# v0_4_4.net
KiCad netlist of a schematic drawn in EAGLE
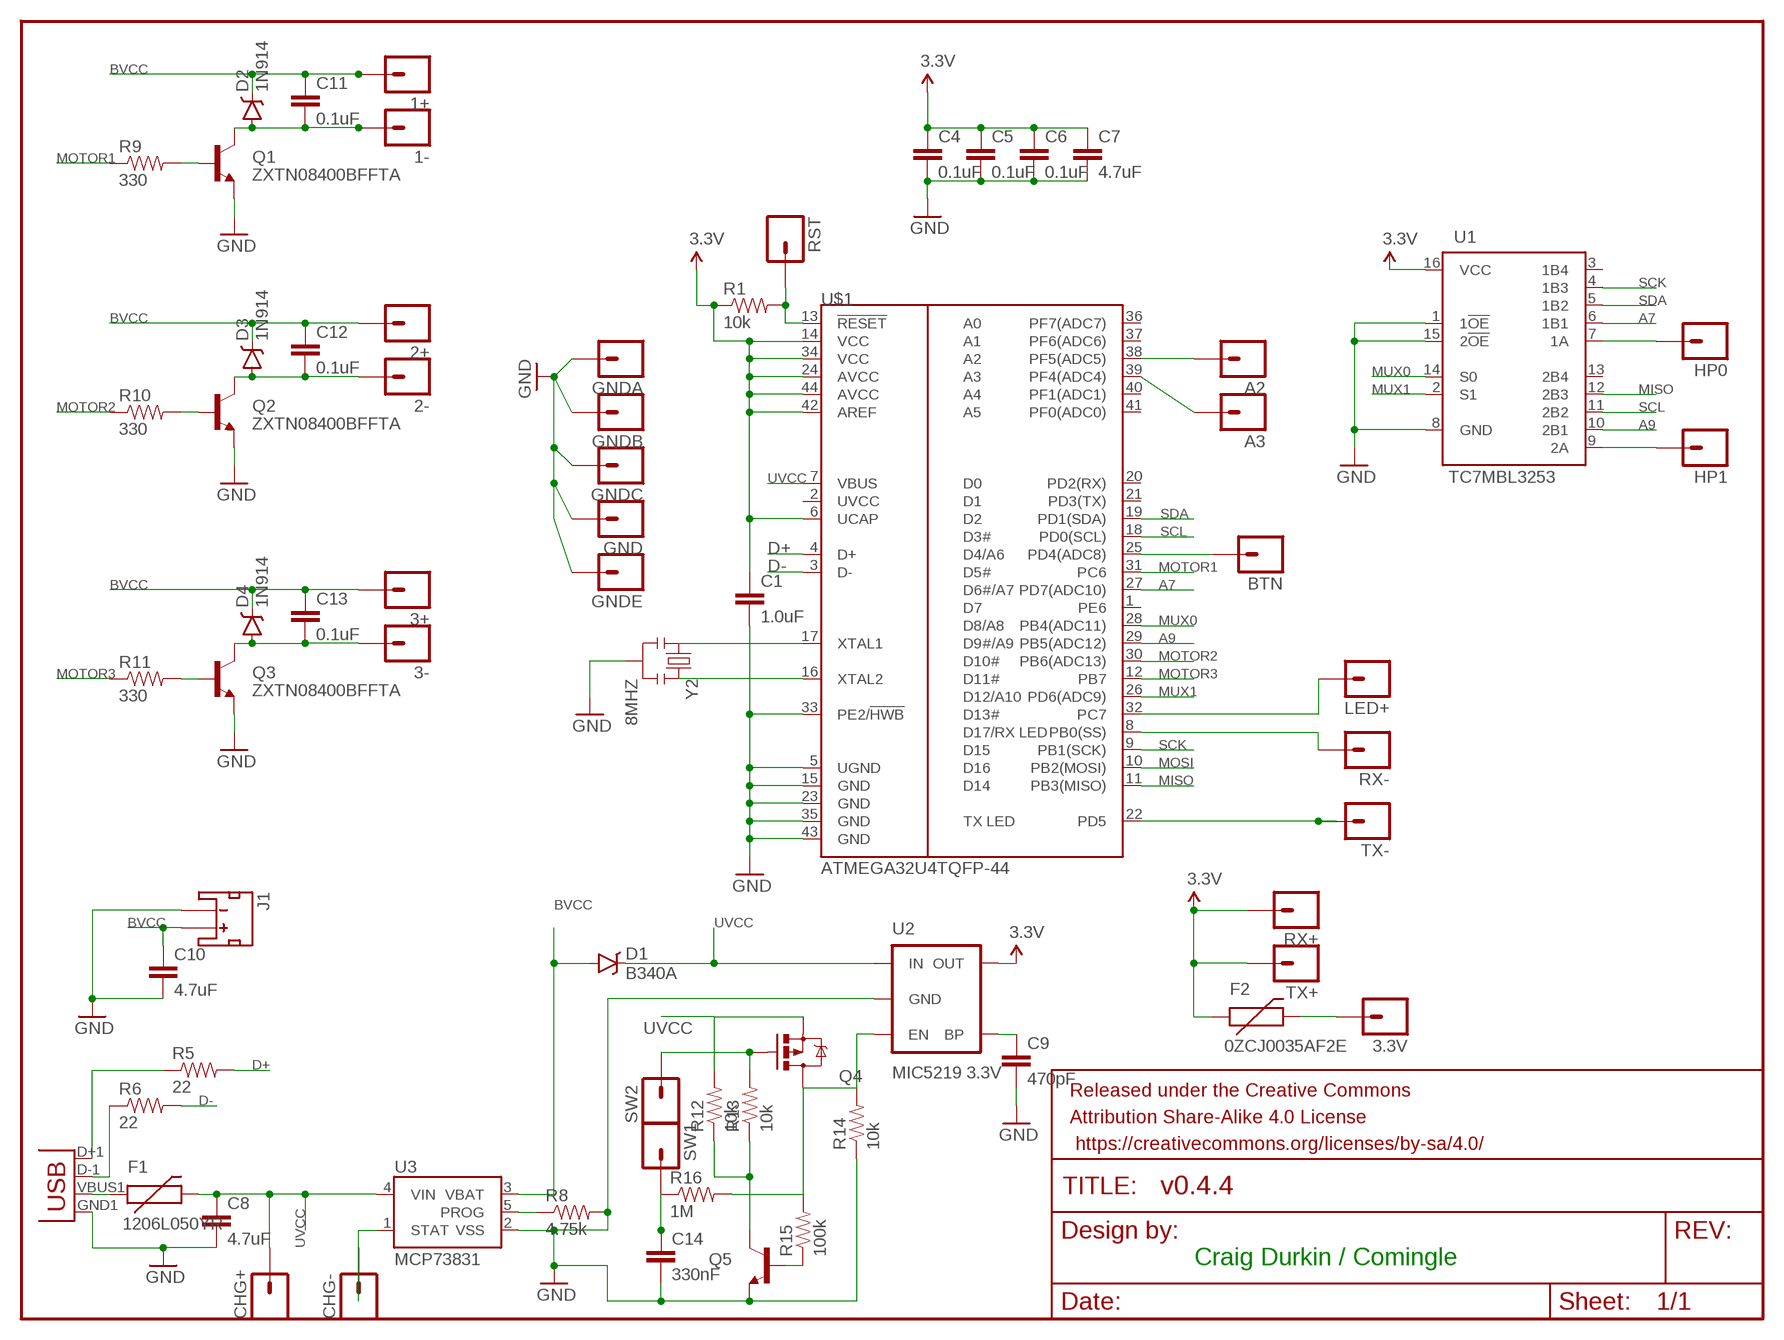
[diagram p0: schematic, sheet 1]

(export (version "E")
  (design (tool "Eeschema 10.0.6"))
  (components
    (comp (ref "1+")
      (value "M01PTH")
      (footprint "eagle-import:1X01")
      (libsource (lib "eagle-import") (part "M01PTH"))
    )
    (comp (ref "1-")
      (value "M01PTH")
      (footprint "eagle-import:1X01")
      (libsource (lib "eagle-import") (part "M01PTH"))
    )
    (comp (ref "2+")
      (value "M01PTH")
      (footprint "eagle-import:1X01")
      (libsource (lib "eagle-import") (part "M01PTH"))
    )
    (comp (ref "2-")
      (value "M01PTH")
      (footprint "eagle-import:1X01")
      (libsource (lib "eagle-import") (part "M01PTH"))
    )
    (comp (ref "3+")
      (value "M01PTH")
      (footprint "eagle-import:1X01")
      (libsource (lib "eagle-import") (part "M01PTH"))
    )
    (comp (ref "3-")
      (value "M01PTH")
      (footprint "eagle-import:1X01")
      (libsource (lib "eagle-import") (part "M01PTH"))
    )
    (comp (ref "3.3V")
      (value "M01PTH")
      (footprint "eagle-import:1X01")
      (libsource (lib "eagle-import") (part "M01PTH"))
    )
    (comp (ref "A2")
      (value "M01PTH")
      (footprint "eagle-import:1X01")
      (libsource (lib "eagle-import") (part "M01PTH"))
    )
    (comp (ref "A3")
      (value "M01PTH")
      (footprint "eagle-import:1X01")
      (libsource (lib "eagle-import") (part "M01PTH"))
    )
    (comp (ref "BTN")
      (value "M01PTH")
      (footprint "eagle-import:1X01")
      (libsource (lib "eagle-import") (part "M01PTH"))
    )
    (comp (ref "C1")
      (value "1.0uF")
      (footprint "eagle-import:0603-CAP")
      (libsource (lib "eagle-import") (part "CAP0603-CAP"))
    )
    (comp (ref "C4")
      (value "0.1uF")
      (footprint "eagle-import:0603-CAP")
      (libsource (lib "eagle-import") (part "SparkFun-Passives_CAP0603-CAP"))
    )
    (comp (ref "C5")
      (value "0.1uF")
      (footprint "eagle-import:0603-CAP")
      (libsource (lib "eagle-import") (part "SparkFun-Passives_CAP0603-CAP"))
    )
    (comp (ref "C6")
      (value "0.1uF")
      (footprint "eagle-import:0603-CAP")
      (libsource (lib "eagle-import") (part "SparkFun-Passives_CAP0603-CAP"))
    )
    (comp (ref "C7")
      (value "4.7uF")
      (footprint "eagle-import:0603-CAP")
      (libsource (lib "eagle-import") (part "SparkFun-Passives_CAP0603-CAP"))
    )
    (comp (ref "C8")
      (value "4.7uF")
      (footprint "eagle-import:1206")
      (libsource (lib "eagle-import") (part "SparkFun-Passives_CAP1206"))
    )
    (comp (ref "C9")
      (value "470pF")
      (footprint "eagle-import:0603-CAP")
      (libsource (lib "eagle-import") (part "CAP0603-CAP"))
    )
    (comp (ref "C10")
      (value "4.7uF")
      (footprint "eagle-import:1206")
      (libsource (lib "eagle-import") (part "SparkFun-Passives_CAP1206"))
    )
    (comp (ref "C11")
      (value "0.1uF")
      (footprint "eagle-import:0603-CAP")
      (libsource (lib "eagle-import") (part "CAP0603-CAP"))
    )
    (comp (ref "C12")
      (value "0.1uF")
      (footprint "eagle-import:0603-CAP")
      (libsource (lib "eagle-import") (part "CAP0603-CAP"))
    )
    (comp (ref "C13")
      (value "0.1uF")
      (footprint "eagle-import:0603-CAP")
      (libsource (lib "eagle-import") (part "CAP0603-CAP"))
    )
    (comp (ref "C14")
      (value "330nF")
      (footprint "eagle-import:0603-CAP")
      (libsource (lib "eagle-import") (part "CAP0603-CAP"))
    )
    (comp (ref "CHG+")
      (value "M01PTH")
      (footprint "eagle-import:1X01")
      (libsource (lib "eagle-import") (part "M01PTH"))
    )
    (comp (ref "CHG-")
      (value "M01PTH")
      (footprint "eagle-import:1X01")
      (libsource (lib "eagle-import") (part "M01PTH"))
    )
    (comp (ref "D1")
      (value "B340A")
      (footprint "eagle-import:SMA-DIODE")
      (libsource (lib "eagle-import") (part "DIODE-SCHOTTKY-B340A"))
    )
    (comp (ref "D2")
      (value "1N914")
      (footprint "eagle-import:SOD-323")
      (libsource (lib "eagle-import") (part "BAT20JFILM"))
    )
    (comp (ref "D3")
      (value "1N914")
      (footprint "eagle-import:SOD-323")
      (libsource (lib "eagle-import") (part "BAT20JFILM"))
    )
    (comp (ref "D4")
      (value "1N914")
      (footprint "eagle-import:SOD-323")
      (libsource (lib "eagle-import") (part "BAT20JFILM"))
    )
    (comp (ref "F1")
      (value "1206L050YR")
      (footprint "eagle-import:PTC-1206")
      (libsource (lib "eagle-import") (part "PTCSMD"))
    )
    (comp (ref "F2")
      (value "0ZCJ0035AF2E")
      (footprint "eagle-import:PTC-1206")
      (libsource (lib "eagle-import") (part "PTCSMD"))
    )
    (comp (ref "FRAME1")
      (value "FRAME-LETTER")
      (footprint "eagle-import:CREATIVE_COMMONS")
      (libsource (lib "eagle-import") (part "FRAME-LETTER"))
    )
    (comp (ref "GND")
      (value "M01PTH")
      (footprint "eagle-import:1X01")
      (libsource (lib "eagle-import") (part "M01PTH"))
    )
    (comp (ref "GNDA")
      (value "M01PTH")
      (footprint "eagle-import:1X01")
      (libsource (lib "eagle-import") (part "M01PTH"))
    )
    (comp (ref "GNDB")
      (value "M01PTH")
      (footprint "eagle-import:1X01")
      (libsource (lib "eagle-import") (part "M01PTH"))
    )
    (comp (ref "GNDC")
      (value "M01PTH")
      (footprint "eagle-import:1X01")
      (libsource (lib "eagle-import") (part "M01PTH"))
    )
    (comp (ref "GNDE")
      (value "M01PTH")
      (footprint "eagle-import:1X01")
      (libsource (lib "eagle-import") (part "M01PTH"))
    )
    (comp (ref "HP0")
      (value "M01PTH")
      (footprint "eagle-import:1X01")
      (libsource (lib "eagle-import") (part "M01PTH"))
    )
    (comp (ref "HP1")
      (value "M01PTH")
      (footprint "eagle-import:1X01")
      (libsource (lib "eagle-import") (part "M01PTH"))
    )
    (comp (ref "J1")
      (value "JST_2MM_MALE")
      (footprint "eagle-import:JST-2-SMD")
      (libsource (lib "eagle-import") (part "JST_2MM_MALE"))
    )
    (comp (ref "JP4")
      (value "USB")
      (footprint "eagle-import:USB-B-MICRO-SMD_V03")
      (libsource (lib "eagle-import") (part "USB"))
    )
    (comp (ref "LED+")
      (value "M01PTH")
      (footprint "eagle-import:1X01")
      (libsource (lib "eagle-import") (part "M01PTH"))
    )
    (comp (ref "Q1")
      (value "ZXTN08400BFFTA")
      (footprint "eagle-import:SOT23-3")
      (libsource (lib "eagle-import") (part "TRANSISTOR_NPNSOT23-3"))
    )
    (comp (ref "Q2")
      (value "ZXTN08400BFFTA")
      (footprint "eagle-import:SOT23-3")
      (libsource (lib "eagle-import") (part "TRANSISTOR_NPNSOT23-3"))
    )
    (comp (ref "Q3")
      (value "ZXTN08400BFFTA")
      (footprint "eagle-import:SOT23-3")
      (libsource (lib "eagle-import") (part "TRANSISTOR_NPNSOT23-3"))
    )
    (comp (ref "Q4")
      (value "NTS2101PT1G")
      (footprint "eagle-import:SOT23-3")
      (libsource (lib "eagle-import") (part "MOSFET-PCHANNEL"))
    )
    (comp (ref "Q5")
      (value "MMBT2222A")
      (footprint "eagle-import:SOT23-3")
      (libsource (lib "eagle-import") (part "TRANSISTOR_NPNMMBT2222A"))
    )
    (comp (ref "R1")
      (value "10k")
      (footprint "eagle-import:0603-RES")
      (libsource (lib "eagle-import") (part "RESISTOR0603-RES"))
    )
    (comp (ref "R5")
      (value "22")
      (footprint "eagle-import:0603-RES")
      (libsource (lib "eagle-import") (part "RESISTOR0603-RES"))
    )
    (comp (ref "R6")
      (value "22")
      (footprint "eagle-import:0603-RES")
      (libsource (lib "eagle-import") (part "RESISTOR0603-RES"))
    )
    (comp (ref "R8")
      (value "4.75k")
      (footprint "eagle-import:0603-RES")
      (libsource (lib "eagle-import") (part "RESISTOR0603-RES"))
    )
    (comp (ref "R9")
      (value "330")
      (footprint "eagle-import:0603-RES")
      (libsource (lib "eagle-import") (part "RESISTOR0603-RES"))
    )
    (comp (ref "R10")
      (value "330")
      (footprint "eagle-import:0603-RES")
      (libsource (lib "eagle-import") (part "RESISTOR0603-RES"))
    )
    (comp (ref "R11")
      (value "330")
      (footprint "eagle-import:0603-RES")
      (libsource (lib "eagle-import") (part "RESISTOR0603-RES"))
    )
    (comp (ref "R12")
      (value "10k")
      (footprint "eagle-import:0603-RES")
      (libsource (lib "eagle-import") (part "RESISTOR0603-RES"))
    )
    (comp (ref "R13")
      (value "10k")
      (footprint "eagle-import:0603-RES")
      (libsource (lib "eagle-import") (part "RESISTOR0603-RES"))
    )
    (comp (ref "R14")
      (value "10k")
      (footprint "eagle-import:0603-RES")
      (libsource (lib "eagle-import") (part "RESISTOR0603-RES"))
    )
    (comp (ref "R15")
      (value "100k")
      (footprint "eagle-import:0603-RES")
      (libsource (lib "eagle-import") (part "RESISTOR0603-RES"))
    )
    (comp (ref "R16")
      (value "1M")
      (footprint "eagle-import:0603-RES")
      (libsource (lib "eagle-import") (part "RESISTOR0603-RES"))
    )
    (comp (ref "RST")
      (value "M01PTH")
      (footprint "eagle-import:1X01")
      (libsource (lib "eagle-import") (part "M01PTH"))
    )
    (comp (ref "RX+")
      (value "M01PTH")
      (footprint "eagle-import:1X01")
      (libsource (lib "eagle-import") (part "M01PTH"))
    )
    (comp (ref "RX-")
      (value "M01PTH")
      (footprint "eagle-import:1X01")
      (libsource (lib "eagle-import") (part "M01PTH"))
    )
    (comp (ref "SW1")
      (value "M01PTH")
      (footprint "eagle-import:1X01")
      (libsource (lib "eagle-import") (part "M01PTH"))
    )
    (comp (ref "SW2")
      (value "M01PTH")
      (footprint "eagle-import:1X01")
      (libsource (lib "eagle-import") (part "M01PTH"))
    )
    (comp (ref "TX+")
      (value "M01PTH")
      (footprint "eagle-import:1X01")
      (libsource (lib "eagle-import") (part "M01PTH"))
    )
    (comp (ref "TX-")
      (value "M01PTH")
      (footprint "eagle-import:1X01")
      (libsource (lib "eagle-import") (part "M01PTH"))
    )
    (comp (ref "U$1")
      (value "ATMEGA32U4TQFP-44")
      (footprint "eagle-import:TQFP44")
      (libsource (lib "eagle-import") (part "ATMEGA32U4TQFP-44"))
    )
    (comp (ref "U1")
      (value "TC7MBL3253")
      (footprint "eagle-import:SSOP16-PRACTICE")
      (libsource (lib "eagle-import") (part "TC7MBL3253"))
    )
    (comp (ref "U2")
      (value "MIC5219 3.3V")
      (footprint "eagle-import:SOT23-5")
      (libsource (lib "eagle-import") (part "V_REG_MIC52193.3V"))
    )
    (comp (ref "U3")
      (value "MCP73831")
      (footprint "eagle-import:SOT23-5")
      (libsource (lib "eagle-import") (part "MCP73831"))
    )
    (comp (ref "Y2")
      (value "8MHZ")
      (footprint "eagle-import:RESONATOR-SMD")
      (libsource (lib "eagle-import") (part "RESONATOR8MHZ"))
    )
  )
  (nets
    (net (code "1") (name "/A7") (class "Default")
      (node (ref "U$1") (pin "27") (pinfunction "PD7(ADC10)_27") (pintype "bidirectional"))
      (node (ref "U1") (pin "6") (pinfunction "1B1_6") (pintype "bidirectional"))
    )
    (net (code "2") (name "/A9") (class "Default")
      (node (ref "U$1") (pin "29") (pinfunction "PB5(ADC12)_29") (pintype "bidirectional"))
      (node (ref "U1") (pin "10") (pinfunction "2B1_10") (pintype "bidirectional"))
    )
    (net (code "3") (name "/BVCC") (class "Default")
      (node (ref "1+") (pin "1") (pinfunction "1_1") (pintype "passive"))
      (node (ref "2+") (pin "1") (pinfunction "1_1") (pintype "passive"))
      (node (ref "3+") (pin "1") (pinfunction "1_1") (pintype "passive"))
      (node (ref "C10") (pin "1") (pinfunction "1_1") (pintype "passive"))
      (node (ref "C11") (pin "1") (pinfunction "1_1") (pintype "passive"))
      (node (ref "C12") (pin "1") (pinfunction "1_1") (pintype "passive"))
      (node (ref "C13") (pin "1") (pinfunction "1_1") (pintype "passive"))
      (node (ref "D1") (pin "A") (pinfunction "A_A") (pintype "passive"))
      (node (ref "D2") (pin "C") (pinfunction "C_C") (pintype "passive"))
      (node (ref "D3") (pin "C") (pinfunction "C_C") (pintype "passive"))
      (node (ref "D4") (pin "C") (pinfunction "C_C") (pintype "passive"))
      (node (ref "J1") (pin "2") (pinfunction "+_2") (pintype "bidirectional"))
      (node (ref "U3") (pin "3") (pinfunction "VBAT_3") (pintype "power_in"))
    )
    (net (code "4") (name "/D+") (class "Default")
      (node (ref "R5") (pin "2") (pinfunction "2_2") (pintype "passive"))
      (node (ref "U$1") (pin "4") (pinfunction "D+_4") (pintype "bidirectional"))
    )
    (net (code "5") (name "/D-") (class "Default")
      (node (ref "R6") (pin "2") (pinfunction "2_2") (pintype "passive"))
      (node (ref "U$1") (pin "3") (pinfunction "D-_3") (pintype "bidirectional"))
    )
    (net (code "6") (name "/MISO") (class "Default")
      (node (ref "U$1") (pin "11") (pinfunction "PB3(MISO)_11") (pintype "bidirectional"))
      (node (ref "U1") (pin "12") (pinfunction "2B3_12") (pintype "bidirectional"))
    )
    (net (code "7") (name "/MOSI") (class "Default")
      (node (ref "U$1") (pin "10") (pinfunction "PB2(MOSI)_10") (pintype "bidirectional"))
    )
    (net (code "8") (name "/MOTOR1") (class "Default")
      (node (ref "R9") (pin "1") (pinfunction "1_1") (pintype "passive"))
      (node (ref "U$1") (pin "31") (pinfunction "PC6_31") (pintype "bidirectional"))
    )
    (net (code "9") (name "/MOTOR2") (class "Default")
      (node (ref "R10") (pin "1") (pinfunction "1_1") (pintype "passive"))
      (node (ref "U$1") (pin "30") (pinfunction "PB6(ADC13)_30") (pintype "bidirectional"))
    )
    (net (code "10") (name "/MOTOR3") (class "Default")
      (node (ref "R11") (pin "1") (pinfunction "1_1") (pintype "passive"))
      (node (ref "U$1") (pin "12") (pinfunction "PB7_12") (pintype "bidirectional"))
    )
    (net (code "11") (name "/MUX0") (class "Default")
      (node (ref "U$1") (pin "28") (pinfunction "PB4(ADC11)_28") (pintype "bidirectional"))
      (node (ref "U1") (pin "14") (pinfunction "S0_14") (pintype "bidirectional"))
    )
    (net (code "12") (name "/MUX1") (class "Default")
      (node (ref "U$1") (pin "26") (pinfunction "PD6(ADC9)_26") (pintype "bidirectional"))
      (node (ref "U1") (pin "2") (pinfunction "S1_2") (pintype "bidirectional"))
    )
    (net (code "13") (name "/SCK") (class "Default")
      (node (ref "U$1") (pin "9") (pinfunction "PB1(SCK)_9") (pintype "bidirectional"))
      (node (ref "U1") (pin "4") (pinfunction "1B3_4") (pintype "bidirectional"))
    )
    (net (code "14") (name "/SCL") (class "Default")
      (node (ref "U$1") (pin "18") (pinfunction "PD0(SCL)_18") (pintype "bidirectional"))
      (node (ref "U1") (pin "11") (pinfunction "2B2_11") (pintype "bidirectional"))
    )
    (net (code "15") (name "/SDA") (class "Default")
      (node (ref "U$1") (pin "19") (pinfunction "PD1(SDA)_19") (pintype "bidirectional"))
      (node (ref "U1") (pin "5") (pinfunction "1B2_5") (pintype "bidirectional"))
    )
    (net (code "16") (name "/UVCC") (class "Default")
      (node (ref "C8") (pin "1") (pinfunction "1_1") (pintype "passive"))
      (node (ref "CHG+") (pin "1") (pinfunction "1_1") (pintype "passive"))
      (node (ref "D1") (pin "C") (pinfunction "C_C") (pintype "passive"))
      (node (ref "F1") (pin "2") (pinfunction "2_2") (pintype "bidirectional"))
      (node (ref "Q4") (pin "2") (pinfunction "S_2") (pintype "passive"))
      (node (ref "R12") (pin "2") (pinfunction "2_2") (pintype "passive"))
      (node (ref "U$1") (pin "7") (pinfunction "VBUS_7") (pintype "bidirectional"))
      (node (ref "U2") (pin "1") (pinfunction "IN_1") (pintype "input"))
      (node (ref "U3") (pin "4") (pinfunction "VIN_4") (pintype "power_in"))
    )
    (net (code "17") (name "3.3V") (class "Default")
      (node (ref "C1") (pin "1") (pinfunction "1_1") (pintype "passive"))
      (node (ref "C4") (pin "1") (pinfunction "1_1") (pintype "passive"))
      (node (ref "C5") (pin "1") (pinfunction "1_1") (pintype "passive"))
      (node (ref "C6") (pin "1") (pinfunction "1_1") (pintype "passive"))
      (node (ref "C7") (pin "1") (pinfunction "1_1") (pintype "passive"))
      (node (ref "F2") (pin "1") (pinfunction "1_1") (pintype "bidirectional"))
      (node (ref "R1") (pin "1") (pinfunction "1_1") (pintype "passive"))
      (node (ref "RX+") (pin "1") (pinfunction "1_1") (pintype "passive"))
      (node (ref "TX+") (pin "1") (pinfunction "1_1") (pintype "passive"))
      (node (ref "U$1") (pin "14") (pinfunction "VCC_14") (pintype "bidirectional"))
      (node (ref "U$1") (pin "24") (pinfunction "AVCC_24") (pintype "bidirectional"))
      (node (ref "U$1") (pin "34") (pinfunction "VCC_34") (pintype "bidirectional"))
      (node (ref "U$1") (pin "42") (pinfunction "AREF_42") (pintype "bidirectional"))
      (node (ref "U$1") (pin "44") (pinfunction "AVCC_44") (pintype "bidirectional"))
      (node (ref "U$1") (pin "6") (pinfunction "UCAP_6") (pintype "bidirectional"))
      (node (ref "U1") (pin "16") (pinfunction "VCC_16") (pintype "power_in"))
      (node (ref "U2") (pin "5") (pinfunction "OUT_5") (pintype "passive"))
    )
    (net (code "18") (name "GND") (class "Default")
      (node (ref "C1") (pin "2") (pinfunction "2_2") (pintype "passive"))
      (node (ref "C10") (pin "2") (pinfunction "2_2") (pintype "passive"))
      (node (ref "C14") (pin "2") (pinfunction "2_2") (pintype "passive"))
      (node (ref "C4") (pin "2") (pinfunction "2_2") (pintype "passive"))
      (node (ref "C5") (pin "2") (pinfunction "2_2") (pintype "passive"))
      (node (ref "C6") (pin "2") (pinfunction "2_2") (pintype "passive"))
      (node (ref "C7") (pin "2") (pinfunction "2_2") (pintype "passive"))
      (node (ref "C8") (pin "2") (pinfunction "2_2") (pintype "passive"))
      (node (ref "C9") (pin "2") (pinfunction "2_2") (pintype "passive"))
      (node (ref "GND") (pin "1") (pinfunction "1_1") (pintype "passive"))
      (node (ref "GNDA") (pin "1") (pinfunction "1_1") (pintype "passive"))
      (node (ref "GNDB") (pin "1") (pinfunction "1_1") (pintype "passive"))
      (node (ref "GNDC") (pin "1") (pinfunction "1_1") (pintype "passive"))
      (node (ref "GNDE") (pin "1") (pinfunction "1_1") (pintype "passive"))
      (node (ref "J1") (pin "1") (pinfunction "-_1") (pintype "bidirectional"))
      (node (ref "JP4") (pin "GND1") (pinfunction "GND_GND1") (pintype "bidirectional"))
      (node (ref "Q1") (pin "2") (pinfunction "E_2") (pintype "passive"))
      (node (ref "Q2") (pin "2") (pinfunction "E_2") (pintype "passive"))
      (node (ref "Q3") (pin "2") (pinfunction "E_2") (pintype "passive"))
      (node (ref "Q5") (pin "2") (pinfunction "E_2") (pintype "passive"))
      (node (ref "R14") (pin "1") (pinfunction "1_1") (pintype "passive"))
      (node (ref "R8") (pin "2") (pinfunction "2_2") (pintype "passive"))
      (node (ref "U$1") (pin "15") (pinfunction "GND_15") (pintype "bidirectional"))
      (node (ref "U$1") (pin "23") (pinfunction "GND_23") (pintype "bidirectional"))
      (node (ref "U$1") (pin "33") (pinfunction "PE2/~{HWB}_33") (pintype "bidirectional"))
      (node (ref "U$1") (pin "35") (pinfunction "GND_35") (pintype "bidirectional"))
      (node (ref "U$1") (pin "43") (pinfunction "GND_43") (pintype "bidirectional"))
      (node (ref "U$1") (pin "5") (pinfunction "UGND_5") (pintype "bidirectional"))
      (node (ref "U1") (pin "1") (pinfunction "1~{OE}_1") (pintype "input"))
      (node (ref "U1") (pin "15") (pinfunction "2~{OE}_15") (pintype "input"))
      (node (ref "U1") (pin "8") (pinfunction "GND_8") (pintype "power_in"))
      (node (ref "U2") (pin "2") (pinfunction "GND_2") (pintype "input"))
      (node (ref "U3") (pin "2") (pinfunction "VSS_2") (pintype "power_in"))
      (node (ref "Y2") (pin "2") (pinfunction "2_2") (pintype "passive"))
    )
    (net (code "19") (name "Net-(3.3V-Pad1)") (class "Default")
      (node (ref "3.3V") (pin "1") (pinfunction "1_1") (pintype "passive"))
      (node (ref "F2") (pin "2") (pinfunction "2_2") (pintype "bidirectional"))
    )
    (net (code "20") (name "Net-(C14-Pad1)") (class "Default")
      (node (ref "C14") (pin "1") (pinfunction "1_1") (pintype "passive"))
      (node (ref "R16") (pin "1") (pinfunction "1_1") (pintype "passive"))
      (node (ref "SW1") (pin "1") (pinfunction "1_1") (pintype "passive"))
    )
    (net (code "21") (name "Net-(JP4-D+)") (class "Default")
      (node (ref "JP4") (pin "D+1") (pinfunction "D+_D+1") (pintype "bidirectional"))
      (node (ref "R5") (pin "1") (pinfunction "1_1") (pintype "passive"))
    )
    (net (code "22") (name "Net-(JP4-D-)") (class "Default")
      (node (ref "JP4") (pin "D-1") (pinfunction "D-_D-1") (pintype "bidirectional"))
      (node (ref "R6") (pin "1") (pinfunction "1_1") (pintype "passive"))
    )
    (net (code "23") (name "Net-(JP4-VBUS)") (class "Default")
      (node (ref "F1") (pin "1") (pinfunction "1_1") (pintype "bidirectional"))
      (node (ref "JP4") (pin "VBUS1") (pinfunction "VBUS_VBUS1") (pintype "bidirectional"))
    )
    (net (code "24") (name "Net-(Q1-B)") (class "Default")
      (node (ref "Q1") (pin "1") (pinfunction "B_1") (pintype "passive"))
      (node (ref "R9") (pin "2") (pinfunction "2_2") (pintype "passive"))
    )
    (net (code "25") (name "Net-(Q1-C)") (class "Default")
      (node (ref "1-") (pin "1") (pinfunction "1_1") (pintype "passive"))
      (node (ref "C11") (pin "2") (pinfunction "2_2") (pintype "passive"))
      (node (ref "D2") (pin "A") (pinfunction "A_A") (pintype "passive"))
      (node (ref "Q1") (pin "3") (pinfunction "C_3") (pintype "passive"))
    )
    (net (code "26") (name "Net-(Q2-B)") (class "Default")
      (node (ref "Q2") (pin "1") (pinfunction "B_1") (pintype "passive"))
      (node (ref "R10") (pin "2") (pinfunction "2_2") (pintype "passive"))
    )
    (net (code "27") (name "Net-(Q2-C)") (class "Default")
      (node (ref "2-") (pin "1") (pinfunction "1_1") (pintype "passive"))
      (node (ref "C12") (pin "2") (pinfunction "2_2") (pintype "passive"))
      (node (ref "D3") (pin "A") (pinfunction "A_A") (pintype "passive"))
      (node (ref "Q2") (pin "3") (pinfunction "C_3") (pintype "passive"))
    )
    (net (code "28") (name "Net-(Q3-B)") (class "Default")
      (node (ref "Q3") (pin "1") (pinfunction "B_1") (pintype "passive"))
      (node (ref "R11") (pin "2") (pinfunction "2_2") (pintype "passive"))
    )
    (net (code "29") (name "Net-(Q3-C)") (class "Default")
      (node (ref "3-") (pin "1") (pinfunction "1_1") (pintype "passive"))
      (node (ref "C13") (pin "2") (pinfunction "2_2") (pintype "passive"))
      (node (ref "D4") (pin "A") (pinfunction "A_A") (pintype "passive"))
      (node (ref "Q3") (pin "3") (pinfunction "C_3") (pintype "passive"))
    )
    (net (code "30") (name "Net-(Q4-D)") (class "Default")
      (node (ref "Q4") (pin "3") (pinfunction "D_3") (pintype "passive"))
      (node (ref "R14") (pin "2") (pinfunction "2_2") (pintype "passive"))
      (node (ref "R15") (pin "2") (pinfunction "2_2") (pintype "passive"))
      (node (ref "R16") (pin "2") (pinfunction "2_2") (pintype "passive"))
      (node (ref "U2") (pin "3") (pinfunction "EN_3") (pintype "input"))
    )
    (net (code "31") (name "Net-(Q4-G)") (class "Default")
      (node (ref "Q4") (pin "1") (pinfunction "G_1") (pintype "passive"))
      (node (ref "R13") (pin "2") (pinfunction "2_2") (pintype "passive"))
      (node (ref "SW2") (pin "1") (pinfunction "1_1") (pintype "passive"))
    )
    (net (code "32") (name "Net-(Q5-B)") (class "Default")
      (node (ref "Q5") (pin "1") (pinfunction "B_1") (pintype "passive"))
      (node (ref "R15") (pin "1") (pinfunction "1_1") (pintype "passive"))
    )
    (net (code "33") (name "Net-(Q5-C)") (class "Default")
      (node (ref "Q5") (pin "3") (pinfunction "C_3") (pintype "passive"))
      (node (ref "R12") (pin "1") (pinfunction "1_1") (pintype "passive"))
      (node (ref "R13") (pin "1") (pinfunction "1_1") (pintype "passive"))
    )
    (net (code "34") (name "Net-(U$1-PB0(SS))") (class "Default")
      (node (ref "RX-") (pin "1") (pinfunction "1_1") (pintype "passive"))
      (node (ref "U$1") (pin "8") (pinfunction "PB0(SS)_8") (pintype "bidirectional"))
    )
    (net (code "35") (name "Net-(U$1-PC7)") (class "Default")
      (node (ref "LED+") (pin "1") (pinfunction "1_1") (pintype "passive"))
      (node (ref "U$1") (pin "32") (pinfunction "PC7_32") (pintype "bidirectional"))
    )
    (net (code "36") (name "Net-(U$1-PD4(ADC8))") (class "Default")
      (node (ref "BTN") (pin "1") (pinfunction "1_1") (pintype "passive"))
      (node (ref "U$1") (pin "25") (pinfunction "PD4(ADC8)_25") (pintype "bidirectional"))
    )
    (net (code "37") (name "Net-(U$1-PD5)") (class "Default")
      (node (ref "TX-") (pin "1") (pinfunction "1_1") (pintype "passive"))
      (node (ref "U$1") (pin "22") (pinfunction "PD5_22") (pintype "bidirectional"))
    )
    (net (code "38") (name "Net-(U$1-PF4(ADC4))") (class "Default")
      (node (ref "A3") (pin "1") (pinfunction "1_1") (pintype "passive"))
      (node (ref "U$1") (pin "39") (pinfunction "PF4(ADC4)_39") (pintype "bidirectional"))
    )
    (net (code "39") (name "Net-(U$1-PF5(ADC5))") (class "Default")
      (node (ref "A2") (pin "1") (pinfunction "1_1") (pintype "passive"))
      (node (ref "U$1") (pin "38") (pinfunction "PF5(ADC5)_38") (pintype "bidirectional"))
    )
    (net (code "40") (name "Net-(U$1-XTAL1)") (class "Default")
      (node (ref "U$1") (pin "17") (pinfunction "XTAL1_17") (pintype "bidirectional"))
      (node (ref "Y2") (pin "1") (pinfunction "1_1") (pintype "passive"))
    )
    (net (code "41") (name "Net-(U$1-XTAL2)") (class "Default")
      (node (ref "U$1") (pin "16") (pinfunction "XTAL2_16") (pintype "bidirectional"))
      (node (ref "Y2") (pin "3") (pinfunction "3_3") (pintype "passive"))
    )
    (net (code "42") (name "Net-(U$1-~{RESET})") (class "Default")
      (node (ref "R1") (pin "2") (pinfunction "2_2") (pintype "passive"))
      (node (ref "RST") (pin "1") (pinfunction "1_1") (pintype "passive"))
      (node (ref "U$1") (pin "13") (pinfunction "~{RESET}_13") (pintype "bidirectional"))
    )
    (net (code "43") (name "Net-(U1-1A)") (class "Default")
      (node (ref "HP0") (pin "1") (pinfunction "1_1") (pintype "passive"))
      (node (ref "U1") (pin "7") (pinfunction "1A_7") (pintype "bidirectional"))
    )
    (net (code "44") (name "Net-(U1-2A)") (class "Default")
      (node (ref "HP1") (pin "1") (pinfunction "1_1") (pintype "passive"))
      (node (ref "U1") (pin "9") (pinfunction "2A_9") (pintype "bidirectional"))
    )
    (net (code "45") (name "Net-(U2-BP)") (class "Default")
      (node (ref "C9") (pin "1") (pinfunction "1_1") (pintype "passive"))
      (node (ref "U2") (pin "4") (pinfunction "BP_4") (pintype "input"))
    )
    (net (code "46") (name "Net-(U3-PROG)") (class "Default")
      (node (ref "R8") (pin "1") (pinfunction "1_1") (pintype "passive"))
      (node (ref "U3") (pin "5") (pinfunction "PROG_5") (pintype "bidirectional"))
    )
    (net (code "47") (name "Net-(U3-STAT)") (class "Default")
      (node (ref "CHG-") (pin "1") (pinfunction "1_1") (pintype "passive"))
      (node (ref "U3") (pin "1") (pinfunction "STAT_1") (pintype "output"))
    )
    (net (code "48") (name "unconnected-(J1-PAD1-PadNC1)") (class "Default")
      (node (ref "J1") (pin "NC1") (pinfunction "PAD1_NC1") (pintype "bidirectional"))
    )
    (net (code "49") (name "unconnected-(J1-PAD2-PadNC2)") (class "Default")
      (node (ref "J1") (pin "NC2") (pinfunction "PAD2_NC2") (pintype "bidirectional"))
    )
    (net (code "50") (name "unconnected-(U$1-PD2(RX)-Pad20)") (class "Default")
      (node (ref "U$1") (pin "20") (pinfunction "PD2(RX)_20") (pintype "bidirectional"))
    )
    (net (code "51") (name "unconnected-(U$1-PD3(TX)-Pad21)") (class "Default")
      (node (ref "U$1") (pin "21") (pinfunction "PD3(TX)_21") (pintype "bidirectional"))
    )
    (net (code "52") (name "unconnected-(U$1-PE6-Pad1)") (class "Default")
      (node (ref "U$1") (pin "1") (pinfunction "PE6_1") (pintype "bidirectional"))
    )
    (net (code "53") (name "unconnected-(U$1-PF0(ADC0)-Pad41)") (class "Default")
      (node (ref "U$1") (pin "41") (pinfunction "PF0(ADC0)_41") (pintype "bidirectional"))
    )
    (net (code "54") (name "unconnected-(U$1-PF1(ADC1)-Pad40)") (class "Default")
      (node (ref "U$1") (pin "40") (pinfunction "PF1(ADC1)_40") (pintype "bidirectional"))
    )
    (net (code "55") (name "unconnected-(U$1-PF6(ADC6)-Pad37)") (class "Default")
      (node (ref "U$1") (pin "37") (pinfunction "PF6(ADC6)_37") (pintype "bidirectional"))
    )
    (net (code "56") (name "unconnected-(U$1-PF7(ADC7)-Pad36)") (class "Default")
      (node (ref "U$1") (pin "36") (pinfunction "PF7(ADC7)_36") (pintype "bidirectional"))
    )
    (net (code "57") (name "unconnected-(U$1-UVCC-Pad2)") (class "Default")
      (node (ref "U$1") (pin "2") (pinfunction "UVCC_2") (pintype "bidirectional"))
    )
    (net (code "58") (name "unconnected-(U1-1B4-Pad3)") (class "Default")
      (node (ref "U1") (pin "3") (pinfunction "1B4_3") (pintype "bidirectional"))
    )
    (net (code "59") (name "unconnected-(U1-2B4-Pad13)") (class "Default")
      (node (ref "U1") (pin "13") (pinfunction "2B4_13") (pintype "bidirectional"))
    )
  )
)
